# Sensors.net
KiCad netlist of a schematic drawn in Altium Designer
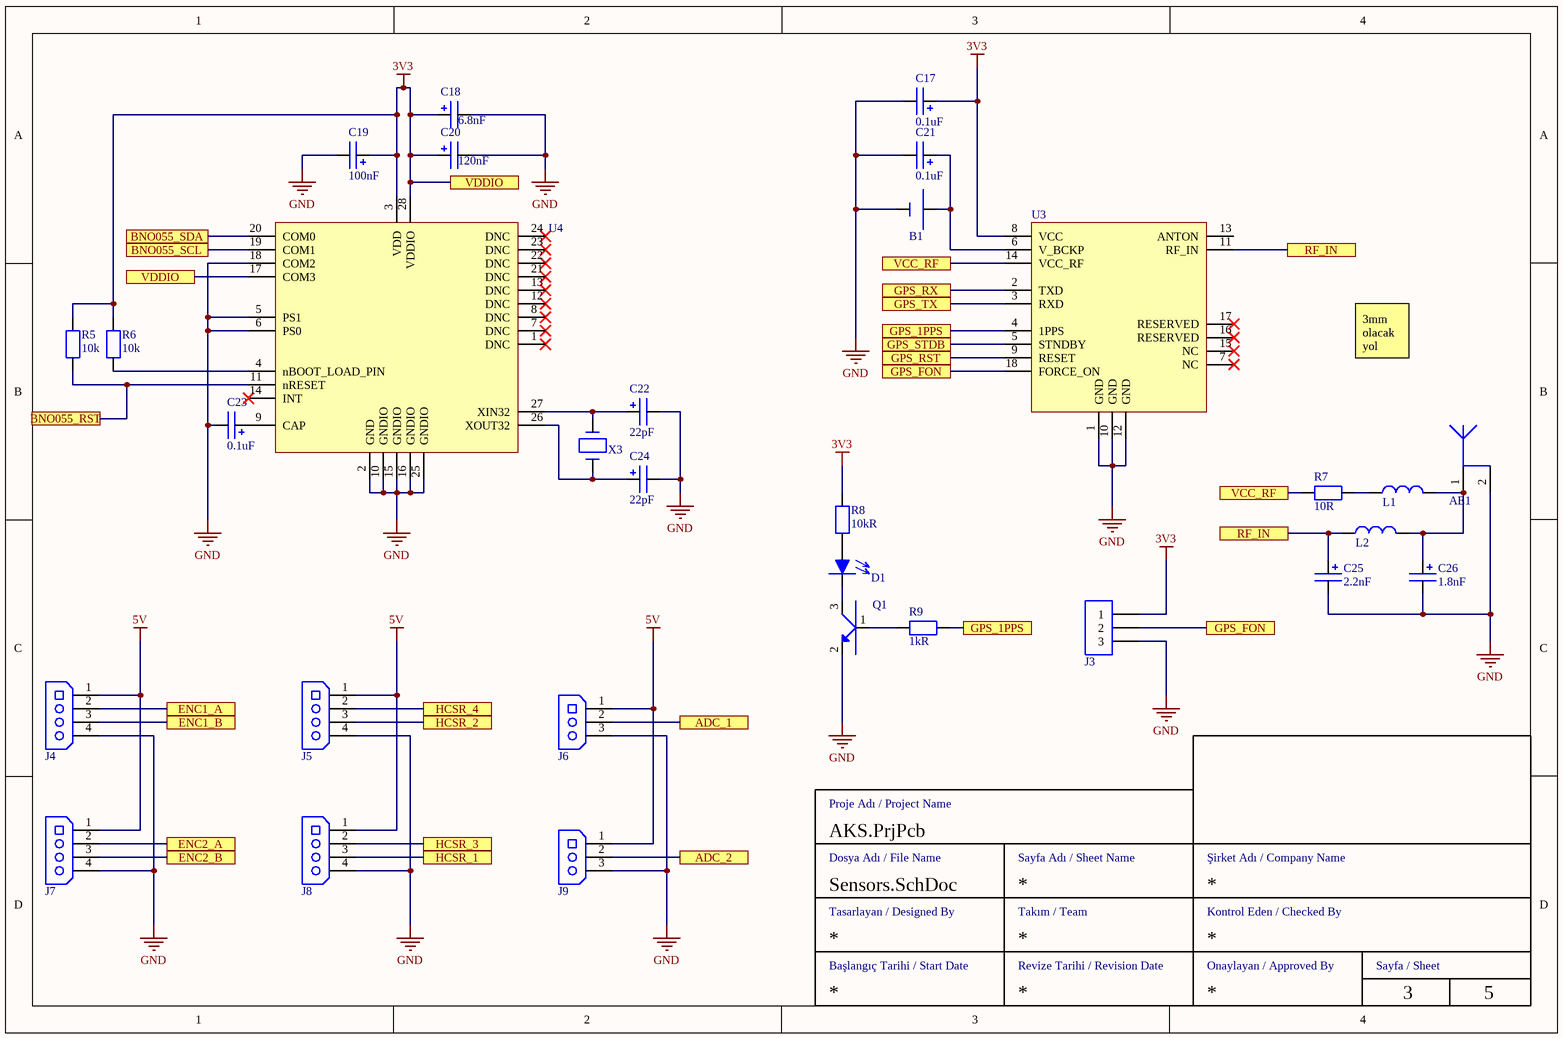
[diagram p0: Sensors.SchDoc]

(export (version "E")
  (design (tool "Eeschema 10.0.6"))
  (components
    (comp (ref "AE1")
      (value "UFL Connector")
      (footprint "UFL CONN")
      (description "Antenna Connector")
      (libsource (lib "Kaptanyums Lib") (part "UFL Connector"))
    )
    (comp (ref "B1")
      (value "BH029")
      (footprint "BH029")
      (description "Battery Holder")
      (libsource (lib "Kaptanyums Lib") (part "BH029"))
    )
    (comp (ref "C17")
      (value "0.1uF")
      (footprint "CAP 0603")
      (description "Multilayer Ceramic Capacitor")
      (fields (field (name "Comment") "CAP 0603"))
      (libsource (lib "Kaptanyums Lib") (part "CAP 0603"))
    )
    (comp (ref "C18")
      (value "6.8nF")
      (footprint "CAP 0603")
      (description "Multilayer Ceramic Capacitor")
      (fields (field (name "Comment") "CAP 0603"))
      (libsource (lib "Kaptanyums Lib") (part "CAP 0603"))
    )
    (comp (ref "C19")
      (value "100nF")
      (footprint "CAP 0603")
      (description "Multilayer Ceramic Capacitor")
      (fields (field (name "Comment") "CAP 0603"))
      (libsource (lib "Kaptanyums Lib") (part "CAP 0603"))
    )
    (comp (ref "C20")
      (value "120nF")
      (footprint "CAP 0603")
      (description "Multilayer Ceramic Capacitor")
      (fields (field (name "Comment") "CAP 0603"))
      (libsource (lib "Kaptanyums Lib") (part "CAP 0603"))
    )
    (comp (ref "C21")
      (value "0.1uF")
      (footprint "CAP 0603")
      (description "Multilayer Ceramic Capacitor")
      (fields (field (name "Comment") "CAP 0603"))
      (libsource (lib "Kaptanyums Lib") (part "CAP 0603"))
    )
    (comp (ref "C22")
      (value "22pF")
      (footprint "CAP 0603")
      (description "Multilayer Ceramic Capacitor")
      (fields (field (name "Comment") "CAP 0603"))
      (libsource (lib "Kaptanyums Lib") (part "CAP 0603"))
    )
    (comp (ref "C23")
      (value "0.1uF")
      (footprint "CAP 0603")
      (description "Multilayer Ceramic Capacitor")
      (fields (field (name "Comment") "CAP 0603"))
      (libsource (lib "Kaptanyums Lib") (part "CAP 0603"))
    )
    (comp (ref "C24")
      (value "22pF")
      (footprint "CAP 0603")
      (description "Multilayer Ceramic Capacitor")
      (fields (field (name "Comment") "CAP 0603"))
      (libsource (lib "Kaptanyums Lib") (part "CAP 0603"))
    )
    (comp (ref "C25")
      (value "2.2nF")
      (footprint "CAP 0603")
      (description "Multilayer Ceramic Capacitor")
      (fields (field (name "Comment") "CAP 0603"))
      (libsource (lib "Kaptanyums Lib") (part "CAP 0603"))
    )
    (comp (ref "C26")
      (value "1.8nF")
      (footprint "CAP 0603")
      (description "Multilayer Ceramic Capacitor")
      (fields (field (name "Comment") "CAP 0603"))
      (libsource (lib "Kaptanyums Lib") (part "CAP 0603"))
    )
    (comp (ref "D1")
      (value "LTW-C191TLA")
      (footprint "LED 0603")
      (description "Chip LED")
      (libsource (lib "Kaptanyums Lib") (part "LED 0603"))
    )
    (comp (ref "J3")
      (value "146285-3")
      (footprint "HMATHT00C31")
      (description "Header for PCB")
      (libsource (lib "Kaptanyums Lib") (part "HMATHT00C31"))
    )
    (comp (ref "J4")
      (value "JSTXH4")
      (footprint "JSTXH4")
      (description "JST Socket for PCB")
      (libsource (lib "Kaptanyums Lib") (part "JSTXH4"))
    )
    (comp (ref "J5")
      (value "JSTXH4")
      (footprint "JSTXH4")
      (description "JST Socket for PCB")
      (libsource (lib "Kaptanyums Lib") (part "JSTXH4"))
    )
    (comp (ref "J6")
      (value "JSTXH3")
      (footprint "JSTXH3")
      (description "JST Socket for PCB")
      (libsource (lib "Kaptanyums Lib") (part "JSTXH3"))
    )
    (comp (ref "J7")
      (value "JSTXH4")
      (footprint "JSTXH4")
      (description "JST Socket for PCB")
      (libsource (lib "Kaptanyums Lib") (part "JSTXH4"))
    )
    (comp (ref "J8")
      (value "JSTXH4")
      (footprint "JSTXH4")
      (description "JST Socket for PCB")
      (libsource (lib "Kaptanyums Lib") (part "JSTXH4"))
    )
    (comp (ref "J9")
      (value "JSTXH3")
      (footprint "JSTXH3")
      (description "JST Socket for PCB")
      (libsource (lib "Kaptanyums Lib") (part "JSTXH3"))
    )
    (comp (ref "L1")
      (value "IND 0603")
      (footprint "INDUCTOR 0603")
      (description "SMD Inductor")
      (libsource (lib "Schlib") (part "IND 0603"))
    )
    (comp (ref "L2")
      (value "IND 0603")
      (footprint "INDUCTOR 0603")
      (description "SMD Inductor")
      (libsource (lib "Schlib") (part "IND 0603"))
    )
    (comp (ref "Q1")
      (value "BC817-40")
      (footprint "SOT23-3")
      (description "Transistor BJT")
      (fields (field (name "VOLTAGE") "45V"))
      (libsource (lib "Kaptanyums Lib") (part "BC817-40"))
    )
    (comp (ref "R5")
      (value "10k")
      (footprint "RESISTOR 0603")
      (description "SMD Chip Resistor")
      (fields (field (name "Comment") "RES 0603"))
      (libsource (lib "Kaptanyums Lib") (part "RES 0603"))
    )
    (comp (ref "R6")
      (value "10k")
      (footprint "RESISTOR 0603")
      (description "SMD Chip Resistor")
      (fields (field (name "Comment") "RES 0603"))
      (libsource (lib "Kaptanyums Lib") (part "RES 0603"))
    )
    (comp (ref "R7")
      (value "10R")
      (footprint "RESISTOR 0603")
      (description "SMD Chip Resistor")
      (fields (field (name "Comment") "RES 0603"))
      (libsource (lib "Kaptanyums Lib") (part "RES 0603"))
    )
    (comp (ref "R8")
      (value "10kR")
      (footprint "RESISTOR 0603")
      (description "SMD Chip Resistor")
      (fields (field (name "Comment") "RES 0603"))
      (libsource (lib "Kaptanyums Lib") (part "RES 0603"))
    )
    (comp (ref "R9")
      (value "1kR")
      (footprint "RESISTOR 0603")
      (description "SMD Chip Resistor")
      (fields (field (name "Comment") "RES 0603"))
      (libsource (lib "Kaptanyums Lib") (part "RES 0603"))
    )
    (comp (ref "U3")
      (value "L76M33")
      (footprint "L76M33")
      (description "GPS, GLONASS, GNSS Transceiver")
      (libsource (lib "Kaptanyums Lib") (part "L76M33"))
    )
    (comp (ref "U4")
      (value "BNO055")
      (footprint "LGA-28")
      (description "IMU Sensor")
      (libsource (lib "Kaptanyums Lib") (part "BNO055"))
    )
    (comp (ref "X3")
      (value "RSM200S-32.768")
      (footprint "4-SOJ")
      (description "CRYSTAL")
      (libsource (lib "Kaptanyums Lib") (part "RSM200S-32.768"))
    )
  )
  (nets
    (net (code "1") (name "/ADC_1") (class "Default")
      (node (ref "J6") (pin "2") (pinfunction "2_2") (pintype "passive"))
    )
    (net (code "2") (name "/ADC_2") (class "Default")
      (node (ref "J9") (pin "2") (pinfunction "2_2") (pintype "passive"))
    )
    (net (code "3") (name "/BNO055_RST") (class "Default")
      (node (ref "R5") (pin "1") (pinfunction "1_1") (pintype "passive"))
      (node (ref "U4") (pin "11") (pinfunction "nRESET_11") (pintype "passive"))
    )
    (net (code "4") (name "/BNO055_SCL") (class "Default")
      (node (ref "U4") (pin "19") (pinfunction "COM1_19") (pintype "passive"))
    )
    (net (code "5") (name "/BNO055_SDA") (class "Default")
      (node (ref "U4") (pin "20") (pinfunction "COM0_20") (pintype "passive"))
    )
    (net (code "6") (name "/ENC1_A") (class "Default")
      (node (ref "J4") (pin "2") (pinfunction "2_2") (pintype "passive"))
    )
    (net (code "7") (name "/ENC1_B") (class "Default")
      (node (ref "J4") (pin "3") (pinfunction "3_3") (pintype "passive"))
    )
    (net (code "8") (name "/ENC2_A") (class "Default")
      (node (ref "J7") (pin "2") (pinfunction "2_2") (pintype "passive"))
    )
    (net (code "9") (name "/ENC2_B") (class "Default")
      (node (ref "J7") (pin "3") (pinfunction "3_3") (pintype "passive"))
    )
    (net (code "10") (name "/GPS_1PPS") (class "Default")
      (node (ref "R9") (pin "2") (pinfunction "2_2") (pintype "passive"))
      (node (ref "U3") (pin "4") (pinfunction "1PPS_4") (pintype "passive"))
    )
    (net (code "11") (name "/GPS_FON") (class "Default")
      (node (ref "J3") (pin "2") (pinfunction "2_2") (pintype "passive"))
      (node (ref "U3") (pin "18") (pinfunction "FORCE_ON_18") (pintype "passive"))
    )
    (net (code "12") (name "/GPS_RST") (class "Default")
      (node (ref "U3") (pin "9") (pinfunction "RESET_9") (pintype "passive"))
    )
    (net (code "13") (name "/GPS_RX") (class "Default")
      (node (ref "U3") (pin "2") (pinfunction "TXD_2") (pintype "passive"))
    )
    (net (code "14") (name "/GPS_STDB") (class "Default")
      (node (ref "U3") (pin "5") (pinfunction "STNDBY_5") (pintype "passive"))
    )
    (net (code "15") (name "/GPS_TX") (class "Default")
      (node (ref "U3") (pin "3") (pinfunction "RXD_3") (pintype "passive"))
    )
    (net (code "16") (name "/HCSR_1") (class "Default")
      (node (ref "J8") (pin "3") (pinfunction "3_3") (pintype "passive"))
    )
    (net (code "17") (name "/HCSR_2") (class "Default")
      (node (ref "J5") (pin "3") (pinfunction "3_3") (pintype "passive"))
    )
    (net (code "18") (name "/HCSR_3") (class "Default")
      (node (ref "J8") (pin "2") (pinfunction "2_2") (pintype "passive"))
    )
    (net (code "19") (name "/HCSR_4") (class "Default")
      (node (ref "J5") (pin "2") (pinfunction "2_2") (pintype "passive"))
    )
    (net (code "20") (name "/RF_IN") (class "Default")
      (node (ref "C25") (pin "1") (pinfunction "1_1") (pintype "passive"))
      (node (ref "L2") (pin "1") (pinfunction "1_1") (pintype "passive"))
      (node (ref "U3") (pin "11") (pinfunction "RF_IN_11") (pintype "passive"))
    )
    (net (code "21") (name "/VCC_RF") (class "Default")
      (node (ref "R7") (pin "1") (pinfunction "1_1") (pintype "passive"))
      (node (ref "U3") (pin "14") (pinfunction "VCC_RF_14") (pintype "passive"))
    )
    (net (code "22") (name "3V3") (class "Default")
      (node (ref "C17") (pin "1") (pinfunction "1_1") (pintype "passive"))
      (node (ref "C18") (pin "1") (pinfunction "1_1") (pintype "passive"))
      (node (ref "C19") (pin "1") (pinfunction "1_1") (pintype "passive"))
      (node (ref "C20") (pin "1") (pinfunction "1_1") (pintype "passive"))
      (node (ref "J3") (pin "1") (pinfunction "1_1") (pintype "passive"))
      (node (ref "R5") (pin "2") (pinfunction "2_2") (pintype "passive"))
      (node (ref "R6") (pin "2") (pinfunction "2_2") (pintype "passive"))
      (node (ref "R8") (pin "2") (pinfunction "2_2") (pintype "passive"))
      (node (ref "U3") (pin "8") (pinfunction "VCC_8") (pintype "passive"))
      (node (ref "U4") (pin "17") (pinfunction "COM3_17") (pintype "passive"))
      (node (ref "U4") (pin "28") (pinfunction "VDDIO_28") (pintype "passive"))
      (node (ref "U4") (pin "3") (pinfunction "VDD_3") (pintype "passive"))
    )
    (net (code "23") (name "5V") (class "Default")
      (node (ref "J4") (pin "1") (pinfunction "1_1") (pintype "passive"))
      (node (ref "J5") (pin "1") (pinfunction "1_1") (pintype "passive"))
      (node (ref "J6") (pin "1") (pinfunction "1_1") (pintype "passive"))
      (node (ref "J7") (pin "1") (pinfunction "1_1") (pintype "passive"))
      (node (ref "J8") (pin "1") (pinfunction "1_1") (pintype "passive"))
      (node (ref "J9") (pin "1") (pinfunction "1_1") (pintype "passive"))
    )
    (net (code "24") (name "GND") (class "Default")
      (node (ref "AE1") (pin "2") (pinfunction "2_2") (pintype "passive"))
      (node (ref "B1") (pin "2") (pinfunction "2_2") (pintype "passive"))
      (node (ref "C17") (pin "2") (pinfunction "2_2") (pintype "passive"))
      (node (ref "C18") (pin "2") (pinfunction "2_2") (pintype "passive"))
      (node (ref "C19") (pin "2") (pinfunction "2_2") (pintype "passive"))
      (node (ref "C20") (pin "2") (pinfunction "2_2") (pintype "passive"))
      (node (ref "C21") (pin "2") (pinfunction "2_2") (pintype "passive"))
      (node (ref "C22") (pin "2") (pinfunction "2_2") (pintype "passive"))
      (node (ref "C23") (pin "2") (pinfunction "2_2") (pintype "passive"))
      (node (ref "C24") (pin "2") (pinfunction "2_2") (pintype "passive"))
      (node (ref "C25") (pin "2") (pinfunction "2_2") (pintype "passive"))
      (node (ref "C26") (pin "2") (pinfunction "2_2") (pintype "passive"))
      (node (ref "J3") (pin "3") (pinfunction "3_3") (pintype "passive"))
      (node (ref "J4") (pin "4") (pinfunction "4_4") (pintype "passive"))
      (node (ref "J5") (pin "4") (pinfunction "4_4") (pintype "passive"))
      (node (ref "J6") (pin "3") (pinfunction "3_3") (pintype "passive"))
      (node (ref "J7") (pin "4") (pinfunction "4_4") (pintype "passive"))
      (node (ref "J8") (pin "4") (pinfunction "4_4") (pintype "passive"))
      (node (ref "J9") (pin "3") (pinfunction "3_3") (pintype "passive"))
      (node (ref "Q1") (pin "2") (pinfunction "S_2") (pintype "passive"))
      (node (ref "U3") (pin "1") (pinfunction "GND_1") (pintype "passive"))
      (node (ref "U3") (pin "10") (pinfunction "GND_10") (pintype "passive"))
      (node (ref "U3") (pin "12") (pinfunction "GND_12") (pintype "passive"))
      (node (ref "U4") (pin "10") (pinfunction "GNDIO_10") (pintype "passive"))
      (node (ref "U4") (pin "15") (pinfunction "GNDIO_15") (pintype "passive"))
      (node (ref "U4") (pin "16") (pinfunction "GNDIO_16") (pintype "passive"))
      (node (ref "U4") (pin "18") (pinfunction "COM2_18") (pintype "passive"))
      (node (ref "U4") (pin "2") (pinfunction "GND_2") (pintype "passive"))
      (node (ref "U4") (pin "25") (pinfunction "GNDIO_25") (pintype "passive"))
      (node (ref "U4") (pin "5") (pinfunction "PS1_5") (pintype "passive"))
      (node (ref "U4") (pin "6") (pinfunction "PS0_6") (pintype "passive"))
    )
    (net (code "25") (name "Net-(AE1-Pad1)") (class "Default")
      (node (ref "AE1") (pin "1") (pinfunction "1_1") (pintype "passive"))
      (node (ref "C26") (pin "1") (pinfunction "1_1") (pintype "passive"))
      (node (ref "L1") (pin "2") (pinfunction "2_2") (pintype "passive"))
      (node (ref "L2") (pin "2") (pinfunction "2_2") (pintype "passive"))
    )
    (net (code "26") (name "Net-(D1-Pad2)") (class "Default")
      (node (ref "D1") (pin "2") (pinfunction "2_2") (pintype "passive"))
      (node (ref "R8") (pin "1") (pinfunction "1_1") (pintype "passive"))
    )
    (net (code "27") (name "Net-(L1-Pad1)") (class "Default")
      (node (ref "L1") (pin "1") (pinfunction "1_1") (pintype "passive"))
      (node (ref "R7") (pin "2") (pinfunction "2_2") (pintype "passive"))
    )
    (net (code "28") (name "Net-(Q1-D)") (class "Default")
      (node (ref "D1") (pin "1") (pinfunction "1_1") (pintype "passive"))
      (node (ref "Q1") (pin "3") (pinfunction "D_3") (pintype "passive"))
    )
    (net (code "29") (name "Net-(Q1-G)") (class "Default")
      (node (ref "Q1") (pin "1") (pinfunction "G_1") (pintype "passive"))
      (node (ref "R9") (pin "1") (pinfunction "1_1") (pintype "passive"))
    )
    (net (code "30") (name "Net-(U3-V_BCKP)") (class "Default")
      (node (ref "B1") (pin "1") (pinfunction "1_1") (pintype "passive"))
      (node (ref "C21") (pin "1") (pinfunction "1_1") (pintype "passive"))
      (node (ref "U3") (pin "6") (pinfunction "V_BCKP_6") (pintype "passive"))
    )
    (net (code "31") (name "Net-(U4-CAP)") (class "Default")
      (node (ref "C23") (pin "1") (pinfunction "1_1") (pintype "passive"))
      (node (ref "U4") (pin "9") (pinfunction "CAP_9") (pintype "passive"))
    )
    (net (code "32") (name "Net-(U4-XIN32)") (class "Default")
      (node (ref "C22") (pin "1") (pinfunction "1_1") (pintype "passive"))
      (node (ref "U4") (pin "27") (pinfunction "XIN32_27") (pintype "passive"))
      (node (ref "X3") (pin "4") (pinfunction "4_4") (pintype "passive"))
    )
    (net (code "33") (name "Net-(U4-XOUT32)") (class "Default")
      (node (ref "C24") (pin "1") (pinfunction "1_1") (pintype "passive"))
      (node (ref "U4") (pin "26") (pinfunction "XOUT32_26") (pintype "passive"))
      (node (ref "X3") (pin "1") (pinfunction "1_1") (pintype "passive"))
    )
    (net (code "34") (name "Net-(U4-nBOOT_LOAD_PIN)") (class "Default")
      (node (ref "R6") (pin "1") (pinfunction "1_1") (pintype "passive"))
      (node (ref "U4") (pin "4") (pinfunction "nBOOT_LOAD_PIN_4") (pintype "passive"))
    )
    (net (code "35") (name "unconnected-(U3-ANTON-Pad13)") (class "Default")
      (node (ref "U3") (pin "13") (pinfunction "ANTON_13") (pintype "passive"))
    )
    (net (code "36") (name "unconnected-(U3-NC-Pad7)") (class "Default")
      (node (ref "U3") (pin "7") (pinfunction "NC_7") (pintype "passive+no_connect"))
    )
    (net (code "37") (name "unconnected-(U3-NC-Pad15)") (class "Default")
      (node (ref "U3") (pin "15") (pinfunction "NC_15") (pintype "passive+no_connect"))
    )
    (net (code "38") (name "unconnected-(U3-RESERVED-Pad16)") (class "Default")
      (node (ref "U3") (pin "16") (pinfunction "RESERVED_16") (pintype "passive+no_connect"))
    )
    (net (code "39") (name "unconnected-(U3-RESERVED-Pad17)") (class "Default")
      (node (ref "U3") (pin "17") (pinfunction "RESERVED_17") (pintype "passive+no_connect"))
    )
    (net (code "40") (name "unconnected-(U4-DNC-Pad1)") (class "Default")
      (node (ref "U4") (pin "1") (pinfunction "DNC_1") (pintype "passive+no_connect"))
    )
    (net (code "41") (name "unconnected-(U4-DNC-Pad7)") (class "Default")
      (node (ref "U4") (pin "7") (pinfunction "DNC_7") (pintype "passive+no_connect"))
    )
    (net (code "42") (name "unconnected-(U4-DNC-Pad8)") (class "Default")
      (node (ref "U4") (pin "8") (pinfunction "DNC_8") (pintype "passive+no_connect"))
    )
    (net (code "43") (name "unconnected-(U4-DNC-Pad12)") (class "Default")
      (node (ref "U4") (pin "12") (pinfunction "DNC_12") (pintype "passive+no_connect"))
    )
    (net (code "44") (name "unconnected-(U4-DNC-Pad13)") (class "Default")
      (node (ref "U4") (pin "13") (pinfunction "DNC_13") (pintype "passive+no_connect"))
    )
    (net (code "45") (name "unconnected-(U4-DNC-Pad21)") (class "Default")
      (node (ref "U4") (pin "21") (pinfunction "DNC_21") (pintype "passive+no_connect"))
    )
    (net (code "46") (name "unconnected-(U4-DNC-Pad22)") (class "Default")
      (node (ref "U4") (pin "22") (pinfunction "DNC_22") (pintype "passive+no_connect"))
    )
    (net (code "47") (name "unconnected-(U4-DNC-Pad23)") (class "Default")
      (node (ref "U4") (pin "23") (pinfunction "DNC_23") (pintype "passive+no_connect"))
    )
    (net (code "48") (name "unconnected-(U4-DNC-Pad24)") (class "Default")
      (node (ref "U4") (pin "24") (pinfunction "DNC_24") (pintype "passive+no_connect"))
    )
    (net (code "49") (name "unconnected-(U4-INT-Pad14)") (class "Default")
      (node (ref "U4") (pin "14") (pinfunction "INT_14") (pintype "passive+no_connect"))
    )
  )
)
